# satellite.net
KiCad netlist of a schematic drawn in Altium Designer
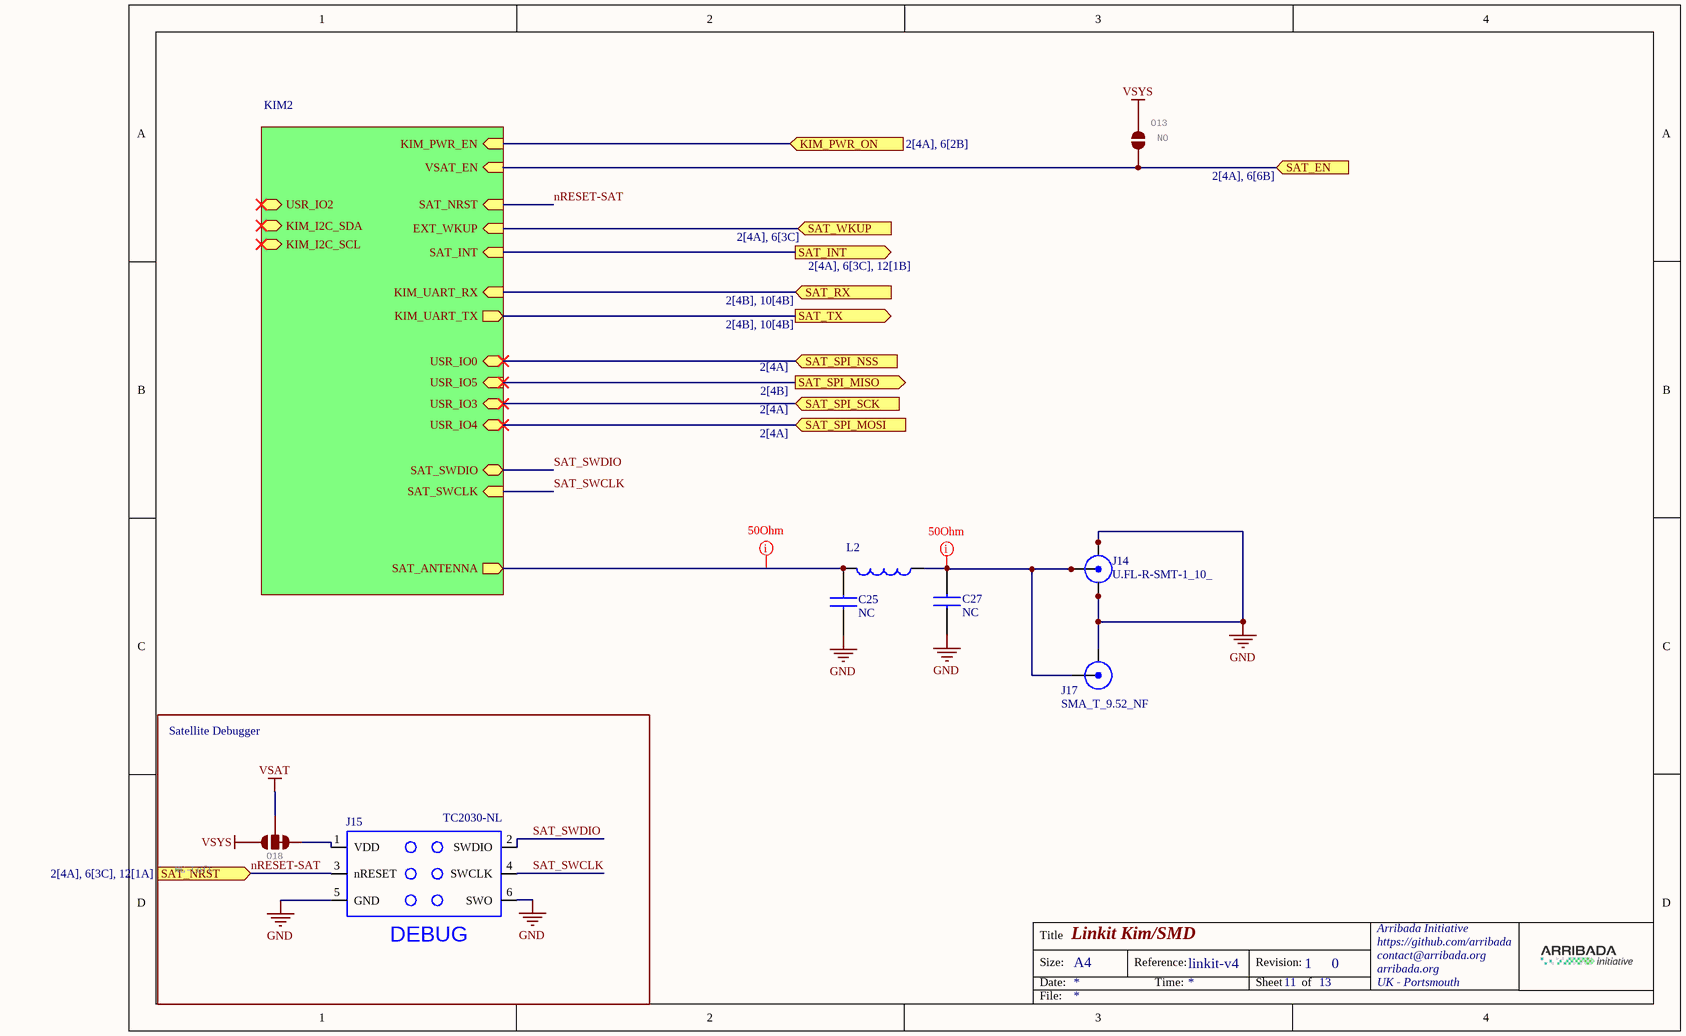
[diagram p0: satellite.SchDoc]

(export (version "E")
  (design (tool "Eeschema 10.0.6"))
  (components
    (comp (ref "C25")
      (value "NC")
      (footprint "CAPC1005X55N")
      (description "Generic capacitor")
      (libsource (lib "stm32wl-dev") (part "GEN_CAP_0402"))
    )
    (comp (ref "C27")
      (value "NC")
      (footprint "CAPC1005X55N")
      (description "Generic capacitor")
      (libsource (lib "stm32wl-dev") (part "GEN_CAP_0402"))
    )
    (comp (ref "J14")
      (value "U.FL-R-SMT-1_10_")
      (footprint "U.FL-R-SMT-1(10)")
      (fields
        (field (name "MOUSER PART NUMBER") "798-U.FL-R-SMT-110")
        (field (name "MANUFACTURER_PART_NUMBER") "U.FL-R-SMT-1(10)")
      )
      (libsource (lib "stm32wl-dev") (part "U.FL-R-SMT-1_10_"))
    )
    (comp (ref "J15")
      (value "TC2030-NL")
      (footprint "TC2030NL")
      (description "CON PLUG OF NAILS 6 PIN FOOTPRINT NO LEGS")
      (fields
        (field (name "MANUFACTURER") "Tag-Connect")
        (field (name "MANUFACTURERS PART NUMBER") "NOT FITTED PART")
      )
      (libsource (lib "Connectors") (part "TC2030-NL"))
    )
    (comp (ref "J17")
      (value "SMA_T_9.52_NF")
      (footprint "CO_SAMTEC_SMA-J-P-ST-EMI")
      (description "SMA End Launch Jack 1.0 mm Board, 50 ohm")
      (fields
        (field (name "MANUFACTURER") "COAX CONNECTORS LTD")
        (field (name "MANUFACTURER_PART_NUMBER") "30-462-D3-1.1mm")
      )
      (libsource (lib "stm32wl-dev") (part "SMA_T_9.52_NF"))
    )
    (comp (ref "L2")
      (value "~")
      (footprint "LQW18AN10NG80D")
      (description "Inductor Wirewound , 18 nH, 75 Milliohm, ± 2%, 1.4 A, 0603 [1608 Metric]")
      (libsource (lib "stm32wl-dev") (part "LQW18AN18NG8ZD"))
    )
    (comp (ref "O13")
      (value "NO")
      (footprint "SMT-JUMPER_2_NO_TRACE_SILK")
      (libsource (lib "stm32wl-dev") (part "JUMPER-SMT_2_NO_TRACE_SILK_1"))
    )
    (comp (ref "O18")
      (value "NC-Left")
      (footprint "SMT-JUMPER_3_2-NCLEFT_TRACE_SILK")
      (libsource (lib "stm32wl-dev") (part "JUMPER-SMT_3_2-NCLEFT_TRACE_SILK"))
    )
  )
  (nets
    (net (code "4") (name "/SAT_ANTENNA") (class "Default")
      (node (ref "C25") (pin "2") (pinfunction "2_2") (pintype "passive"))
      (node (ref "L2") (pin "2") (pinfunction "2_2") (pintype "passive"))
    )
    (net (code "5") (name "/SAT_EN") (class "Default")
      (node (ref "O13") (pin "2") (pinfunction "2_2") (pintype "passive"))
    )
    (net (code "12") (name "/SAT_SWCLK") (class "Default")
      (node (ref "J15") (pin "4") (pinfunction "SWCLK_4") (pintype "passive"))
    )
    (net (code "13") (name "/SAT_SWDIO") (class "Default")
      (node (ref "J15") (pin "2") (pinfunction "SWDIO_2") (pintype "passive"))
    )
    (net (code "17") (name "/nRESET-SAT") (class "Default")
      (node (ref "J15") (pin "3") (pinfunction "nRESET_3") (pintype "passive"))
    )
    (net (code "18") (name "GND") (class "Default")
      (node (ref "C25") (pin "1") (pinfunction "1_1") (pintype "passive"))
      (node (ref "C27") (pin "1") (pinfunction "1_1") (pintype "passive"))
      (node (ref "J14") (pin "1") (pinfunction "Y_1") (pintype "passive"))
      (node (ref "J14") (pin "2") (pinfunction "Y_2") (pintype "passive"))
      (node (ref "J15") (pin "5") (pinfunction "GND_5") (pintype "passive"))
      (node (ref "J15") (pin "6") (pinfunction "SWO_6") (pintype "passive"))
      (node (ref "J17") (pin "2") (pinfunction "Y_2") (pintype "passive"))
    )
    (net (code "19") (name "Net-(J14-X)") (class "Default")
      (node (ref "C27") (pin "2") (pinfunction "2_2") (pintype "passive"))
      (node (ref "J14") (pin "3") (pinfunction "X_3") (pintype "passive"))
      (node (ref "J17") (pin "1") (pinfunction "X_1") (pintype "passive"))
      (node (ref "L2") (pin "1") (pinfunction "1_1") (pintype "passive"))
    )
    (net (code "20") (name "Net-(J15-VDD)") (class "Default")
      (node (ref "J15") (pin "1") (pinfunction "VDD_1") (pintype "passive"))
      (node (ref "O18") (pin "1") (pinfunction "1_1") (pintype "passive"))
    )
    (net (code "21") (name "VSAT") (class "Default")
      (node (ref "O18") (pin "2") (pinfunction "2_2") (pintype "passive"))
    )
    (net (code "22") (name "VSYS") (class "Default")
      (node (ref "O13") (pin "1") (pinfunction "1_1") (pintype "passive"))
      (node (ref "O18") (pin "3") (pinfunction "3_3") (pintype "passive"))
    )
  )
)
